# rgb_dimmer_1.net
KiCad netlist of a schematic drawn in EAGLE
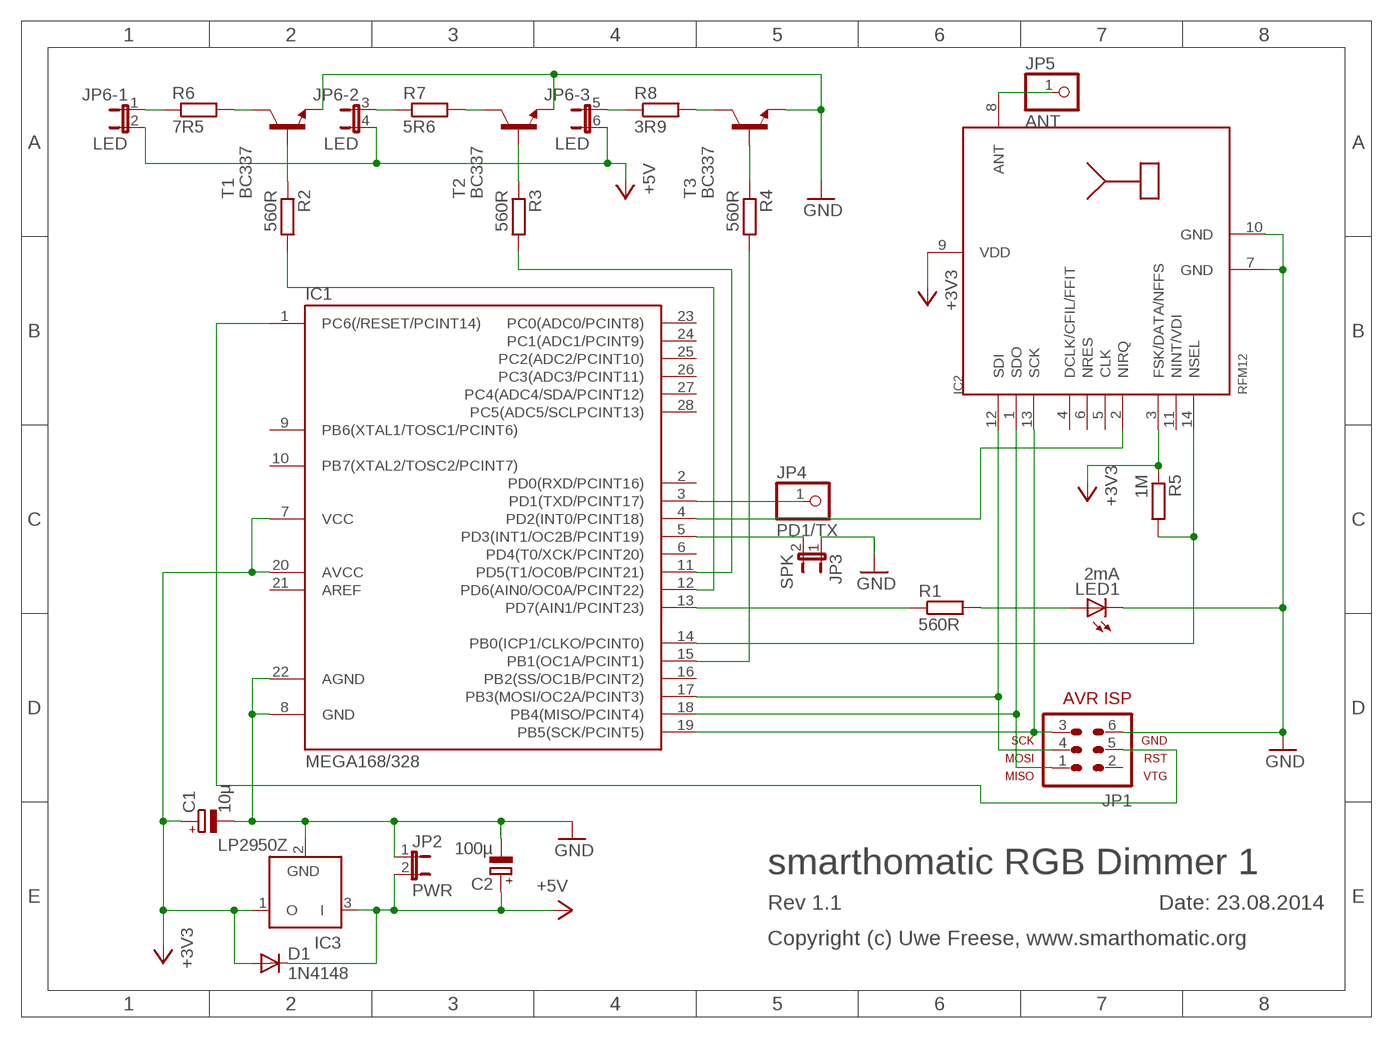
[diagram p0: schematic, sheet 1]

(export (version "E")
  (design (tool "Eeschema 10.0.6"))
  (components
    (comp (ref "C1")
      (value "10µ")
      (footprint "eagle-import:E1,8-4")
      (libsource (lib "eagle-import") (part "CPOL-EUE1.8-4"))
    )
    (comp (ref "C2")
      (value "100µ")
      (footprint "eagle-import:E2,5-6")
      (libsource (lib "eagle-import") (part "CPOL-EUE2.5-6"))
    )
    (comp (ref "D1")
      (value "1N4148")
      (footprint "eagle-import:DO35-7")
      (libsource (lib "eagle-import") (part "1N4148DO35-7"))
    )
    (comp (ref "IC1")
      (value "MEGA168/328")
      (footprint "eagle-import:DIL28-3")
      (libsource (lib "eagle-import") (part "MEGA48/88/168-PU"))
    )
    (comp (ref "IC2")
      (value "RFM12")
      (footprint "eagle-import:RFM")
      (libsource (lib "eagle-import") (part "RFM12"))
    )
    (comp (ref "IC3")
      (value "LP2950Z")
      (footprint "eagle-import:TO92")
      (libsource (lib "eagle-import") (part "LP2950Z"))
    )
    (comp (ref "JP1")
      (value "AVR-ISP-6")
      (footprint "eagle-import:AVR-ISP-6")
      (libsource (lib "eagle-import") (part "AVR-ISP-6"))
    )
    (comp (ref "JP2")
      (value "PWR")
      (footprint "eagle-import:JP1")
      (libsource (lib "eagle-import") (part "JP1E"))
    )
    (comp (ref "JP3")
      (value "SPK")
      (footprint "eagle-import:JP1")
      (libsource (lib "eagle-import") (part "JP1E"))
    )
    (comp (ref "JP4")
      (value "PD1/TX")
      (footprint "eagle-import:1X01")
      (libsource (lib "eagle-import") (part "PINHD-1X1"))
    )
    (comp (ref "JP5")
      (value "ANT")
      (footprint "eagle-import:1X01")
      (libsource (lib "eagle-import") (part "PINHD-1X1"))
    )
    (comp (ref "JP6")
      (value "LED")
      (footprint "eagle-import:JP3Q")
      (libsource (lib "eagle-import") (part "JP3QE"))
    )
    (comp (ref "LED1")
      (value "2mA")
      (footprint "eagle-import:LED3MM")
      (libsource (lib "eagle-import") (part "LED3MM"))
    )
    (comp (ref "R1")
      (value "560R")
      (footprint "eagle-import:0207_7")
      (libsource (lib "eagle-import") (part "R-EU_0207/7"))
    )
    (comp (ref "R2")
      (value "560R")
      (footprint "eagle-import:0207_7")
      (libsource (lib "eagle-import") (part "R-EU_0207/7"))
    )
    (comp (ref "R3")
      (value "560R")
      (footprint "eagle-import:0207_7")
      (libsource (lib "eagle-import") (part "R-EU_0207/7"))
    )
    (comp (ref "R4")
      (value "560R")
      (footprint "eagle-import:0207_7")
      (libsource (lib "eagle-import") (part "R-EU_0207/7"))
    )
    (comp (ref "R5")
      (value "1M")
      (footprint "eagle-import:0207_7")
      (libsource (lib "eagle-import") (part "R-EU_0207/7"))
    )
    (comp (ref "R6")
      (value "7R5")
      (footprint "eagle-import:0207_7")
      (libsource (lib "eagle-import") (part "R-EU_0207/7"))
    )
    (comp (ref "R7")
      (value "5R6")
      (footprint "eagle-import:0207_7")
      (libsource (lib "eagle-import") (part "R-EU_0207/7"))
    )
    (comp (ref "R8")
      (value "3R9")
      (footprint "eagle-import:0207_7")
      (libsource (lib "eagle-import") (part "R-EU_0207/7"))
    )
    (comp (ref "T1")
      (value "BC337")
      (footprint "eagle-import:TO92")
      (libsource (lib "eagle-import") (part "BC337"))
    )
    (comp (ref "T2")
      (value "BC337")
      (footprint "eagle-import:TO92")
      (libsource (lib "eagle-import") (part "BC337"))
    )
    (comp (ref "T3")
      (value "BC337")
      (footprint "eagle-import:TO92")
      (libsource (lib "eagle-import") (part "BC337"))
    )
  )
  (nets
    (net (code "1") (name "+3V3") (class "Default")
      (node (ref "C1") (pin "+") (pinfunction "+_+") (pintype "passive"))
      (node (ref "D1") (pin "A") (pinfunction "A_A") (pintype "passive"))
      (node (ref "IC1") (pin "20") (pinfunction "AVCC_20") (pintype "passive"))
      (node (ref "IC1") (pin "7") (pinfunction "VCC_7") (pintype "power_in"))
      (node (ref "IC2") (pin "3") (pinfunction "FSK/DATA/NFFS_3") (pintype "bidirectional"))
      (node (ref "IC2") (pin "9") (pinfunction "VDD_9") (pintype "power_in"))
      (node (ref "IC3") (pin "1") (pinfunction "O_1") (pintype "input"))
      (node (ref "R5") (pin "1") (pinfunction "1_1") (pintype "passive"))
    )
    (net (code "2") (name "+5V") (class "Default")
      (node (ref "C2") (pin "+") (pinfunction "+_+") (pintype "passive"))
      (node (ref "D1") (pin "C") (pinfunction "C_C") (pintype "passive"))
      (node (ref "IC3") (pin "3") (pinfunction "I_3") (pintype "input"))
      (node (ref "JP2") (pin "2") (pinfunction "2_2") (pintype "passive"))
      (node (ref "JP6") (pin "2") (pinfunction "2_2") (pintype "passive"))
      (node (ref "JP6") (pin "4") (pinfunction "2_4") (pintype "passive"))
      (node (ref "JP6") (pin "6") (pinfunction "2_6") (pintype "passive"))
    )
    (net (code "3") (name "GND") (class "Default")
      (node (ref "C1") (pin "-") (pinfunction "-_-") (pintype "passive"))
      (node (ref "C2") (pin "-") (pinfunction "-_-") (pintype "passive"))
      (node (ref "IC1") (pin "22") (pinfunction "AGND_22") (pintype "power_in"))
      (node (ref "IC1") (pin "8") (pinfunction "GND_8") (pintype "power_in"))
      (node (ref "IC2") (pin "10") (pinfunction "GND_10") (pintype "power_in"))
      (node (ref "IC2") (pin "7") (pinfunction "GND_7") (pintype "power_in"))
      (node (ref "IC3") (pin "2") (pinfunction "GND_2") (pintype "power_in"))
      (node (ref "JP1") (pin "6") (pinfunction "6_6") (pintype "passive"))
      (node (ref "JP2") (pin "1") (pinfunction "1_1") (pintype "passive"))
      (node (ref "JP3") (pin "1") (pinfunction "1_1") (pintype "passive"))
      (node (ref "LED1") (pin "K") (pinfunction "C_K") (pintype "passive"))
      (node (ref "T1") (pin "1") (pinfunction "E_1") (pintype "passive"))
      (node (ref "T2") (pin "1") (pinfunction "E_1") (pintype "passive"))
      (node (ref "T3") (pin "1") (pinfunction "E_1") (pintype "passive"))
    )
    (net (code "4") (name "Net-(IC1-PB0(ICP1{slash}CLKO{slash}PCINT0))") (class "Default")
      (node (ref "IC1") (pin "14") (pinfunction "PB0(ICP1/CLKO/PCINT0)_14") (pintype "bidirectional"))
      (node (ref "IC2") (pin "14") (pinfunction "NSEL_14") (pintype "bidirectional"))
      (node (ref "R5") (pin "2") (pinfunction "2_2") (pintype "passive"))
    )
    (net (code "5") (name "Net-(IC1-PB1(OC1A{slash}PCINT1))") (class "Default")
      (node (ref "IC1") (pin "15") (pinfunction "PB1(OC1A/PCINT1)_15") (pintype "bidirectional"))
      (node (ref "R4") (pin "2") (pinfunction "2_2") (pintype "passive"))
    )
    (net (code "6") (name "Net-(IC1-PB3(MOSI{slash}OC2A{slash}PCINT3))") (class "Default")
      (node (ref "IC1") (pin "17") (pinfunction "PB3(MOSI/OC2A/PCINT3)_17") (pintype "bidirectional"))
      (node (ref "IC2") (pin "12") (pinfunction "SDI_12") (pintype "bidirectional"))
      (node (ref "JP1") (pin "4") (pinfunction "4_4") (pintype "passive"))
    )
    (net (code "7") (name "Net-(IC1-PB4(MISO{slash}PCINT4))") (class "Default")
      (node (ref "IC1") (pin "18") (pinfunction "PB4(MISO/PCINT4)_18") (pintype "bidirectional"))
      (node (ref "IC2") (pin "1") (pinfunction "SDO_1") (pintype "bidirectional"))
      (node (ref "JP1") (pin "1") (pinfunction "1_1") (pintype "passive"))
    )
    (net (code "8") (name "Net-(IC1-PB5(SCK{slash}PCINT5))") (class "Default")
      (node (ref "IC1") (pin "19") (pinfunction "PB5(SCK/PCINT5)_19") (pintype "bidirectional"))
      (node (ref "IC2") (pin "13") (pinfunction "SCK_13") (pintype "bidirectional"))
      (node (ref "JP1") (pin "3") (pinfunction "3_3") (pintype "passive"))
    )
    (net (code "9") (name "Net-(IC1-PC6({slash}RESET{slash}PCINT14))") (class "Default")
      (node (ref "IC1") (pin "1") (pinfunction "PC6(/RESET/PCINT14)_1") (pintype "bidirectional"))
      (node (ref "JP1") (pin "5") (pinfunction "5_5") (pintype "passive"))
    )
    (net (code "10") (name "Net-(IC1-PD1(TXD{slash}PCINT17))") (class "Default")
      (node (ref "IC1") (pin "3") (pinfunction "PD1(TXD/PCINT17)_3") (pintype "bidirectional"))
      (node (ref "JP4") (pin "1") (pinfunction "1_1") (pintype "passive"))
    )
    (net (code "11") (name "Net-(IC1-PD2(INT0{slash}PCINT18))") (class "Default")
      (node (ref "IC1") (pin "4") (pinfunction "PD2(INT0/PCINT18)_4") (pintype "bidirectional"))
      (node (ref "IC2") (pin "2") (pinfunction "NIRQ_2") (pintype "bidirectional"))
    )
    (net (code "12") (name "Net-(IC1-PD3(INT1{slash}OC2B{slash}PCINT19))") (class "Default")
      (node (ref "IC1") (pin "5") (pinfunction "PD3(INT1/OC2B/PCINT19)_5") (pintype "bidirectional"))
      (node (ref "JP3") (pin "2") (pinfunction "2_2") (pintype "passive"))
    )
    (net (code "13") (name "Net-(IC1-PD5(T1{slash}OC0B{slash}PCINT21))") (class "Default")
      (node (ref "IC1") (pin "11") (pinfunction "PD5(T1/OC0B/PCINT21)_11") (pintype "bidirectional"))
      (node (ref "R3") (pin "2") (pinfunction "2_2") (pintype "passive"))
    )
    (net (code "14") (name "Net-(IC1-PD6(AIN0{slash}OC0A{slash}PCINT22))") (class "Default")
      (node (ref "IC1") (pin "12") (pinfunction "PD6(AIN0/OC0A/PCINT22)_12") (pintype "bidirectional"))
      (node (ref "R2") (pin "2") (pinfunction "2_2") (pintype "passive"))
    )
    (net (code "15") (name "Net-(IC1-PD7(AIN1{slash}PCINT23))") (class "Default")
      (node (ref "IC1") (pin "13") (pinfunction "PD7(AIN1/PCINT23)_13") (pintype "bidirectional"))
      (node (ref "R1") (pin "1") (pinfunction "1_1") (pintype "passive"))
    )
    (net (code "16") (name "Net-(IC2-ANT)") (class "Default")
      (node (ref "IC2") (pin "8") (pinfunction "ANT_8") (pintype "output"))
      (node (ref "JP5") (pin "1") (pinfunction "1_1") (pintype "passive"))
    )
    (net (code "17") (name "Net-(JP6-Pad1)") (class "Default")
      (node (ref "JP6") (pin "1") (pinfunction "1_1") (pintype "passive"))
      (node (ref "R6") (pin "1") (pinfunction "1_1") (pintype "passive"))
    )
    (net (code "18") (name "Net-(JP6B-1)") (class "Default")
      (node (ref "JP6") (pin "3") (pinfunction "1_3") (pintype "passive"))
      (node (ref "R7") (pin "1") (pinfunction "1_1") (pintype "passive"))
    )
    (net (code "19") (name "Net-(JP6C-1)") (class "Default")
      (node (ref "JP6") (pin "5") (pinfunction "1_5") (pintype "passive"))
      (node (ref "R8") (pin "1") (pinfunction "1_1") (pintype "passive"))
    )
    (net (code "20") (name "Net-(LED1-PadA)") (class "Default")
      (node (ref "LED1") (pin "A") (pinfunction "A_A") (pintype "passive"))
      (node (ref "R1") (pin "2") (pinfunction "2_2") (pintype "passive"))
    )
    (net (code "21") (name "Net-(T1-B)") (class "Default")
      (node (ref "R2") (pin "1") (pinfunction "1_1") (pintype "passive"))
      (node (ref "T1") (pin "2") (pinfunction "B_2") (pintype "passive"))
    )
    (net (code "22") (name "Net-(T1-C)") (class "Default")
      (node (ref "R6") (pin "2") (pinfunction "2_2") (pintype "passive"))
      (node (ref "T1") (pin "3") (pinfunction "C_3") (pintype "passive"))
    )
    (net (code "23") (name "Net-(T2-B)") (class "Default")
      (node (ref "R3") (pin "1") (pinfunction "1_1") (pintype "passive"))
      (node (ref "T2") (pin "2") (pinfunction "B_2") (pintype "passive"))
    )
    (net (code "24") (name "Net-(T2-C)") (class "Default")
      (node (ref "R7") (pin "2") (pinfunction "2_2") (pintype "passive"))
      (node (ref "T2") (pin "3") (pinfunction "C_3") (pintype "passive"))
    )
    (net (code "25") (name "Net-(T3-B)") (class "Default")
      (node (ref "R4") (pin "1") (pinfunction "1_1") (pintype "passive"))
      (node (ref "T3") (pin "2") (pinfunction "B_2") (pintype "passive"))
    )
    (net (code "26") (name "Net-(T3-C)") (class "Default")
      (node (ref "R8") (pin "2") (pinfunction "2_2") (pintype "passive"))
      (node (ref "T3") (pin "3") (pinfunction "C_3") (pintype "passive"))
    )
    (net (code "27") (name "unconnected-(IC1-AREF-Pad21)") (class "Default")
      (node (ref "IC1") (pin "21") (pinfunction "AREF_21") (pintype "passive"))
    )
    (net (code "28") (name "unconnected-(IC1-PB2(SS{slash}OC1B{slash}PCINT2)-Pad16)") (class "Default")
      (node (ref "IC1") (pin "16") (pinfunction "PB2(SS/OC1B/PCINT2)_16") (pintype "bidirectional"))
    )
    (net (code "29") (name "unconnected-(IC1-PB6(XTAL1{slash}TOSC1{slash}PCINT6)-Pad9)") (class "Default")
      (node (ref "IC1") (pin "9") (pinfunction "PB6(XTAL1/TOSC1/PCINT6)_9") (pintype "bidirectional"))
    )
    (net (code "30") (name "unconnected-(IC1-PB7(XTAL2{slash}TOSC2{slash}PCINT7)-Pad10)") (class "Default")
      (node (ref "IC1") (pin "10") (pinfunction "PB7(XTAL2/TOSC2/PCINT7)_10") (pintype "bidirectional"))
    )
    (net (code "31") (name "unconnected-(IC1-PC0(ADC0{slash}PCINT8)-Pad23)") (class "Default")
      (node (ref "IC1") (pin "23") (pinfunction "PC0(ADC0/PCINT8)_23") (pintype "bidirectional"))
    )
    (net (code "32") (name "unconnected-(IC1-PC1(ADC1{slash}PCINT9)-Pad24)") (class "Default")
      (node (ref "IC1") (pin "24") (pinfunction "PC1(ADC1/PCINT9)_24") (pintype "bidirectional"))
    )
    (net (code "33") (name "unconnected-(IC1-PC2(ADC2{slash}PCINT10)-Pad25)") (class "Default")
      (node (ref "IC1") (pin "25") (pinfunction "PC2(ADC2/PCINT10)_25") (pintype "bidirectional"))
    )
    (net (code "34") (name "unconnected-(IC1-PC3(ADC3{slash}PCINT11)-Pad26)") (class "Default")
      (node (ref "IC1") (pin "26") (pinfunction "PC3(ADC3/PCINT11)_26") (pintype "bidirectional"))
    )
    (net (code "35") (name "unconnected-(IC1-PC4(ADC4{slash}SDA{slash}PCINT12)-Pad27)") (class "Default")
      (node (ref "IC1") (pin "27") (pinfunction "PC4(ADC4/SDA/PCINT12)_27") (pintype "bidirectional"))
    )
    (net (code "36") (name "unconnected-(IC1-PC5(ADC5{slash}SCLPCINT13)-Pad28)") (class "Default")
      (node (ref "IC1") (pin "28") (pinfunction "PC5(ADC5/SCLPCINT13)_28") (pintype "bidirectional"))
    )
    (net (code "37") (name "unconnected-(IC1-PD0(RXD{slash}PCINT16)-Pad2)") (class "Default")
      (node (ref "IC1") (pin "2") (pinfunction "PD0(RXD/PCINT16)_2") (pintype "bidirectional"))
    )
    (net (code "38") (name "unconnected-(IC1-PD4(T0{slash}XCK{slash}PCINT20)-Pad6)") (class "Default")
      (node (ref "IC1") (pin "6") (pinfunction "PD4(T0/XCK/PCINT20)_6") (pintype "bidirectional"))
    )
    (net (code "39") (name "unconnected-(IC2-CLK-Pad5)") (class "Default")
      (node (ref "IC2") (pin "5") (pinfunction "CLK_5") (pintype "bidirectional"))
    )
    (net (code "40") (name "unconnected-(IC2-DCLK{slash}CFIL{slash}FFIT-Pad4)") (class "Default")
      (node (ref "IC2") (pin "4") (pinfunction "DCLK/CFIL/FFIT_4") (pintype "bidirectional"))
    )
    (net (code "41") (name "unconnected-(IC2-NINT{slash}VDI-Pad11)") (class "Default")
      (node (ref "IC2") (pin "11") (pinfunction "NINT/VDI_11") (pintype "bidirectional"))
    )
    (net (code "42") (name "unconnected-(IC2-NRES-Pad6)") (class "Default")
      (node (ref "IC2") (pin "6") (pinfunction "NRES_6") (pintype "bidirectional"))
    )
    (net (code "43") (name "unconnected-(JP1-Pad2)") (class "Default")
      (node (ref "JP1") (pin "2") (pinfunction "2_2") (pintype "passive"))
    )
  )
)
